# Morpheus_LDO.net
KiCad netlist of a schematic drawn in Altium Designer
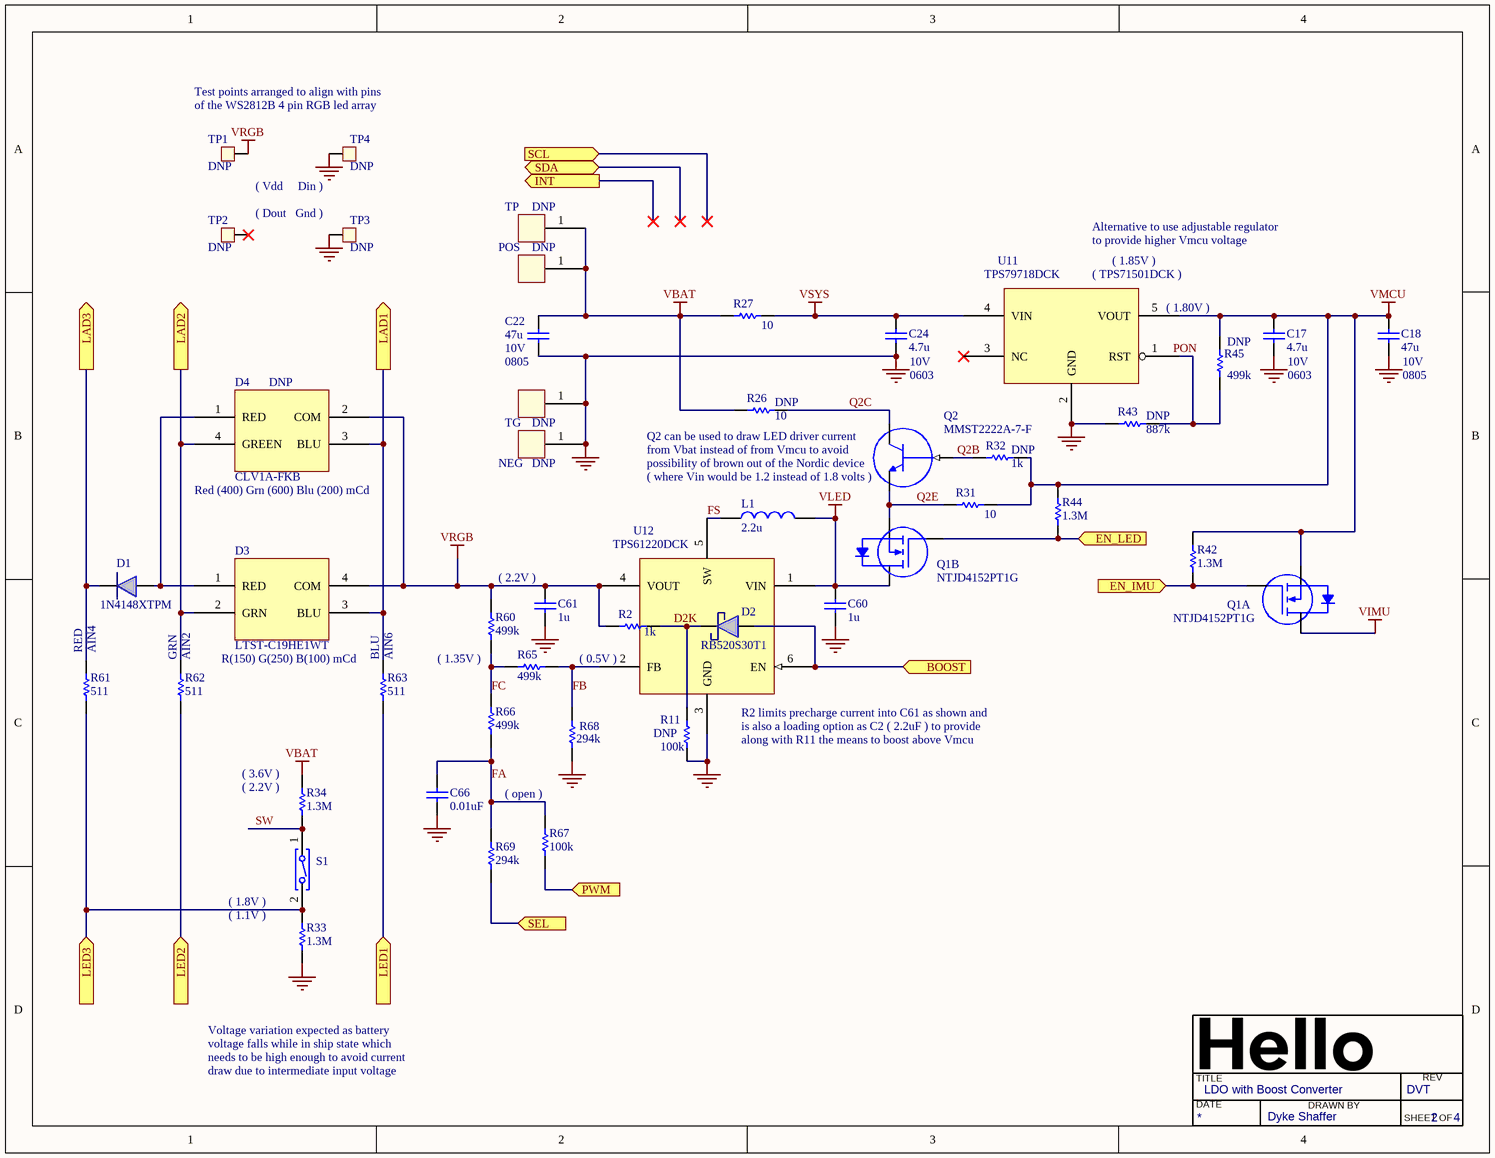
[diagram p0: Morpheus_LDO.SchDoc]

(export (version "E")
  (design (tool "Eeschema 10.0.6"))
  (components
    (comp (ref "C17")
      (value "4.7u")
      (footprint "CAP0603_SENSE_DVT")
      (description "Chip capacitor")
      (fields (field (name "SIZE") "0603") (field (name "TOLERANCE") "20%") (field (name "VOLTAGE") "10V"))
      (libsource (lib "Hello") (part "C_4.7u_20_10_X5R_0603"))
    )
    (comp (ref "C18")
      (value "47u")
      (footprint "CAP0805_SENSE_DVT")
      (description "Chip capacitor")
      (fields (field (name "SIZE") "0805") (field (name "TOLERANCE") "20%") (field (name "VOLTAGE") "10V"))
      (libsource (lib "Hello") (part "C_47u_20_10_X5R_0805"))
    )
    (comp (ref "C22")
      (value "47u")
      (footprint "CAP0805_SENSE_DVT")
      (description "Chip capacitor")
      (fields (field (name "SIZE") "0805") (field (name "TOLERANCE") "20%") (field (name "VOLTAGE") "10V"))
      (libsource (lib "Hello") (part "C_47u_20_10_X5R_0805"))
    )
    (comp (ref "C24")
      (value "4.7u")
      (footprint "CAP0603_SENSE_DVT")
      (description "Chip capacitor")
      (fields (field (name "SIZE") "0603") (field (name "TOLERANCE") "20%") (field (name "VOLTAGE") "10V"))
      (libsource (lib "Hello") (part "C_4.7u_20_10_X5R_0603"))
    )
    (comp (ref "C60")
      (value "1u")
      (footprint "CAP0402_SENSE_DVT")
      (description "Chip capacitor")
      (fields (field (name "TOLERANCE") "10%") (field (name "VOLTAGE") "6.3V"))
      (libsource (lib "Hello") (part "C_1u_10_6.3_X5R_0402"))
    )
    (comp (ref "C61")
      (value "1u")
      (footprint "CAP0402_SENSE_DVT")
      (description "Chip capacitor")
      (fields (field (name "TOLERANCE") "10%") (field (name "VOLTAGE") "6.3V"))
      (libsource (lib "Hello") (part "C_1u_10_6.3_X5R_0402"))
    )
    (comp (ref "C66")
      (value "0.01uF")
      (footprint "CAP0402_SENSE_DVT")
      (description "Chip capacitor")
      (fields (field (name "TOLERANCE") "10%") (field (name "VOLTAGE") "50"))
      (libsource (lib "Hello") (part "C_10000p_10_50_X7R_0402"))
    )
    (comp (ref "D1")
      (value "1N4148XTPM")
      (footprint "SOD523")
      (description "Silicon diode, 30V 200mA")
      (libsource (lib "Hello") (part "1N4148XTPM"))
    )
    (comp (ref "D2")
      (value "RB520S30T1")
      (footprint "SOD523")
      (description "Schottky diode, 30V 200mA")
      (libsource (lib "dykes") (part "RB520S30T1"))
    )
    (comp (ref "D3")
      (value "LTST-C19HE1WT")
      (footprint "DFN120X85P160X160X35-4R")
      (description "RGB LED Array")
      (fields (field (name "ALTIUM_VALUE") "R(150) G(250) B(100) mCd"))
      (libsource (lib "dykes") (part "LTST-C19HE1WT"))
    )
    (comp (ref "D4")
      (value "DNP")
      (footprint "PLCC150X290P280X320X35-4")
      (description "RGB LED Array")
      (fields
        (field (name "PN") "CLV1A-FKB")
        (field (name "ALTIUM_VALUE") "Red (400) Grn (600) Blu (200) mCd")
      )
      (libsource (lib "Hello") (part "CLV1A-FKB"))
    )
    (comp (ref "L1")
      (value "2.2u")
      (footprint "IND_1206")
      (description "SMD power inductor, 2.2uH")
      (fields (field (name "TOLERANCE") "20%"))
      (libsource (lib "Hello") (part "L_2.2u_1206"))
    )
    (comp (ref "NEG")
      (value "DNP")
      (footprint "TP0875x050")
      (description "Single-pad test point")
      (libsource (lib "Mopd") (part "5016"))
    )
    (comp (ref "POS")
      (value "DNP")
      (footprint "TP0875x050")
      (description "Single-pad test point")
      (libsource (lib "Mopd") (part "5016"))
    )
    (comp (ref "Q1")
      (value "NTJD4152PT1G")
      (footprint "SOT65P212X110-6N")
      (description "Vishay Dual N-Channel MOSFET 1.2v drive 20V 0.88A")
      (libsource (lib "Hello") (part "NTJD4152PT1G"))
    )
    (comp (ref "Q2")
      (value "MMST2222A")
      (footprint "SOT-323")
      (description "NPN Transistor, 20V, 600mA")
      (fields (field (name "PN") "MMST2222A-7-F"))
      (libsource (lib "Hello") (part "MMST2222A"))
    )
    (comp (ref "R2")
      (value "1k")
      (footprint "RES0402_SENSE_DVT")
      (description "Chip Resistor")
      (fields (field (name "TOLERANCE") "1 %") (field (name "POWER") "0.1 W"))
      (libsource (lib "Hello") (part "R_1k_1_0.1_0402"))
    )
    (comp (ref "R11")
      (value "DNP")
      (footprint "RES0402_SENSE_DVT")
      (description "Chip Resistor")
      (fields
        (field (name "ALTIUM_VALUE") "100k")
        (field (name "TOLERANCE") "1 %")
        (field (name "POWER") "0.1 W")
      )
      (libsource (lib "Hello") (part "R_100k_1_0.1_0402"))
    )
    (comp (ref "R26")
      (value "DNP")
      (footprint "RES0402_SENSE_DVT")
      (description "Chip Resistor")
      (fields
        (field (name "ALTIUM_VALUE") "10")
        (field (name "TOLERANCE") "1 %")
        (field (name "POWER") "0.1 W")
      )
      (libsource (lib "Hello") (part "R_10_1_0.1_0402"))
    )
    (comp (ref "R27")
      (value "10")
      (footprint "RES0402_SENSE_DVT")
      (description "Chip Resistor")
      (fields (field (name "TOLERANCE") "1 %") (field (name "POWER") "0.1 W"))
      (libsource (lib "Hello") (part "R_10_1_0.1_0402"))
    )
    (comp (ref "R31")
      (value "10")
      (footprint "RES0402_SENSE_DVT")
      (description "Chip Resistor")
      (fields (field (name "TOLERANCE") "1 %") (field (name "POWER") "0.1 W"))
      (libsource (lib "Hello") (part "R_10_1_0.1_0402"))
    )
    (comp (ref "R32")
      (value "DNP")
      (footprint "RES0402_SENSE_DVT")
      (description "Chip Resistor")
      (fields
        (field (name "ALTIUM_VALUE") "1k")
        (field (name "TOLERANCE") "1 %")
        (field (name "POWER") "0.1 W")
      )
      (libsource (lib "Hello") (part "R_1k_1_0.1_0402"))
    )
    (comp (ref "R33")
      (value "1.3M")
      (footprint "RES0402_SENSE_DVT")
      (description "Chip Resistor")
      (fields (field (name "TOLERANCE") "5 %") (field (name "POWER") "0.1 W"))
      (libsource (lib "Hello") (part "R_1.3M_5_0.1_0402"))
    )
    (comp (ref "R34")
      (value "1.3M")
      (footprint "RES0402_SENSE_DVT")
      (description "Chip Resistor")
      (fields (field (name "TOLERANCE") "5 %") (field (name "POWER") "0.1 W"))
      (libsource (lib "Hello") (part "R_1.3M_5_0.1_0402"))
    )
    (comp (ref "R42")
      (value "1.3M")
      (footprint "RES0402_SENSE_DVT")
      (description "Chip Resistor")
      (fields (field (name "TOLERANCE") "5 %") (field (name "POWER") "0.1 W"))
      (libsource (lib "Hello") (part "R_1.3M_5_0.1_0402"))
    )
    (comp (ref "R43")
      (value "DNP")
      (footprint "RES0402_SENSE_DVT")
      (description "Chip Resistor")
      (fields
        (field (name "ALTIUM_VALUE") "887k")
        (field (name "TOLERANCE") "1 %")
        (field (name "POWER") "0.1 W")
      )
      (libsource (lib "Hello") (part "R_887k_1_0.1_0402"))
    )
    (comp (ref "R44")
      (value "1.3M")
      (footprint "RES0402_SENSE_DVT")
      (description "Chip Resistor")
      (fields (field (name "TOLERANCE") "5 %") (field (name "POWER") "0.1 W"))
      (libsource (lib "Hello") (part "R_1.3M_5_0.1_0402"))
    )
    (comp (ref "R45")
      (value "DNP")
      (footprint "RES0402_SENSE_DVT")
      (description "Chip Resistor")
      (fields
        (field (name "ALTIUM_VALUE") "499k")
        (field (name "TOLERANCE") "1 %")
        (field (name "POWER") "0.1 W")
      )
      (libsource (lib "Hello") (part "R_499k_1_0.1_0402"))
    )
    (comp (ref "R60")
      (value "499k")
      (footprint "RES0402_SENSE_DVT")
      (description "Chip Resistor")
      (fields (field (name "TOLERANCE") "1 %") (field (name "POWER") "0.1 W"))
      (libsource (lib "Hello") (part "R_499k_1_0.1_0402"))
    )
    (comp (ref "R61")
      (value "511")
      (footprint "RES0402_SENSE_DVT")
      (description "Chip Resistor")
      (fields (field (name "TOLERANCE") "1 %") (field (name "POWER") "0.1 W"))
      (libsource (lib "Hello") (part "R_511_1_0.1_0402"))
    )
    (comp (ref "R62")
      (value "511")
      (footprint "RES0402_SENSE_DVT")
      (description "Chip Resistor")
      (fields (field (name "TOLERANCE") "1 %") (field (name "POWER") "0.1 W"))
      (libsource (lib "Hello") (part "R_511_1_0.1_0402"))
    )
    (comp (ref "R63")
      (value "511")
      (footprint "RES0402_SENSE_DVT")
      (description "Chip Resistor")
      (fields (field (name "TOLERANCE") "1 %") (field (name "POWER") "0.1 W"))
      (libsource (lib "Hello") (part "R_511_1_0.1_0402"))
    )
    (comp (ref "R65")
      (value "499k")
      (footprint "RES0402_SENSE_DVT")
      (description "Chip Resistor")
      (fields (field (name "TOLERANCE") "1 %") (field (name "POWER") "0.1 W"))
      (libsource (lib "Hello") (part "R_499k_1_0.1_0402"))
    )
    (comp (ref "R66")
      (value "499k")
      (footprint "RES0402_SENSE_DVT")
      (description "Chip Resistor")
      (fields (field (name "TOLERANCE") "1 %") (field (name "POWER") "0.1 W"))
      (libsource (lib "Hello") (part "R_499k_1_0.1_0402"))
    )
    (comp (ref "R67")
      (value "100k")
      (footprint "RES0402_SENSE_DVT")
      (description "Chip Resistor")
      (fields (field (name "TOLERANCE") "1 %") (field (name "POWER") "0.1 W"))
      (libsource (lib "Hello") (part "R_100k_1_0.1_0402"))
    )
    (comp (ref "R68")
      (value "294k")
      (footprint "RES0402_SENSE_DVT")
      (description "Chip Resistor")
      (fields (field (name "TOLERANCE") "1 %") (field (name "POWER") "0.1 W"))
      (libsource (lib "Hello") (part "R_294k_1_0.1_0402"))
    )
    (comp (ref "R69")
      (value "294k")
      (footprint "RES0402_SENSE_DVT")
      (description "Chip Resistor")
      (fields (field (name "TOLERANCE") "1 %") (field (name "POWER") "0.1 W"))
      (libsource (lib "Hello") (part "R_294k_1_0.1_0402"))
    )
    (comp (ref "S1")
      (value "REED_SPST_NO")
      (footprint "REED-10x1.8")
      (description "SWITCH REED SPST NO")
      (libsource (lib "Hello") (part "SW_REED_SPST_NO"))
    )
    (comp (ref "TG")
      (value "DNP")
      (footprint "TP0875x050")
      (description "Single-pad test point")
      (libsource (lib "Mopd") (part "5016"))
    )
    (comp (ref "TP")
      (value "DNP")
      (footprint "TP0875x050")
      (description "Single-pad test point")
      (libsource (lib "Mopd") (part "5016"))
    )
    (comp (ref "TP1")
      (value "DNP")
      (footprint "TP-0.8")
      (description "testpoint")
      (libsource (lib "Hello") (part "TP-0.8"))
    )
    (comp (ref "TP2")
      (value "DNP")
      (footprint "TP-0.8")
      (description "testpoint")
      (libsource (lib "Hello") (part "TP-0.8"))
    )
    (comp (ref "TP3")
      (value "DNP")
      (footprint "TP-0.8")
      (description "testpoint")
      (libsource (lib "") (part "TP-0.8_1"))
    )
    (comp (ref "TP4")
      (value "DNP")
      (footprint "TP-0.8")
      (description "testpoint")
      (libsource (lib "") (part "TP-0.8_1"))
    )
    (comp (ref "U11")
      (value "TPS79718DCK")
      (footprint "SOT65P212X110-5N")
      (description "LDO 1.8V SC70-5")
      (libsource (lib "Hello") (part "TPS79718DCK"))
    )
    (comp (ref "U12")
      (value "TPS61220DCK")
      (footprint "SOT65P212X110-6N")
      (description "Boost Converter")
      (libsource (lib "dykes") (part "TPS61220"))
    )
  )
  (nets
    (net (code "1") (name "/BOOST") (class "Default")
      (node (ref "D2") (pin "2") (pinfunction "Anode_2") (pintype "passive"))
      (node (ref "U12") (pin "6") (pinfunction "EN_6") (pintype "input"))
    )
    (net (code "2") (name "/D2K") (class "Default")
      (node (ref "D2") (pin "1") (pinfunction "Cathode_1") (pintype "passive"))
      (node (ref "R11") (pin "2") (pinfunction "2_2") (pintype "passive"))
      (node (ref "R2") (pin "2") (pinfunction "2_2") (pintype "passive"))
    )
    (net (code "3") (name "/EN_IMU") (class "Default")
      (node (ref "Q1") (pin "2") (pinfunction "G1_2") (pintype "passive"))
      (node (ref "R42") (pin "1") (pinfunction "1_1") (pintype "passive"))
    )
    (net (code "4") (name "/EN_LED") (class "Default")
      (node (ref "Q1") (pin "5") (pinfunction "G2_5") (pintype "passive"))
      (node (ref "R44") (pin "1") (pinfunction "1_1") (pintype "passive"))
    )
    (net (code "5") (name "/FA") (class "Default")
      (node (ref "C66") (pin "2") (pinfunction "2_2") (pintype "passive"))
      (node (ref "R66") (pin "1") (pinfunction "1_1") (pintype "passive"))
      (node (ref "R67") (pin "2") (pinfunction "2_2") (pintype "passive"))
      (node (ref "R69") (pin "2") (pinfunction "2_2") (pintype "passive"))
    )
    (net (code "6") (name "/FB") (class "Default")
      (node (ref "R65") (pin "1") (pinfunction "1_1") (pintype "passive"))
      (node (ref "R68") (pin "2") (pinfunction "2_2") (pintype "passive"))
      (node (ref "U12") (pin "2") (pinfunction "FB_2") (pintype "passive"))
    )
    (net (code "7") (name "/FC") (class "Default")
      (node (ref "R60") (pin "1") (pinfunction "1_1") (pintype "passive"))
      (node (ref "R65") (pin "2") (pinfunction "2_2") (pintype "passive"))
      (node (ref "R66") (pin "2") (pinfunction "2_2") (pintype "passive"))
    )
    (net (code "8") (name "/FS") (class "Default")
      (node (ref "L1") (pin "2") (pintype "passive"))
      (node (ref "U12") (pin "5") (pinfunction "SW_5") (pintype "passive"))
    )
    (net (code "10") (name "/LAD1") (class "Default")
      (node (ref "D3") (pin "3") (pinfunction "BLU_3") (pintype "passive"))
      (node (ref "D4") (pin "3") (pinfunction "BLU_3") (pintype "passive"))
      (node (ref "R63") (pin "2") (pinfunction "2_2") (pintype "passive"))
    )
    (net (code "11") (name "/LAD2") (class "Default")
      (node (ref "D3") (pin "2") (pinfunction "GRN_2") (pintype "passive"))
      (node (ref "D4") (pin "4") (pinfunction "GREEN_4") (pintype "passive"))
      (node (ref "R62") (pin "2") (pinfunction "2_2") (pintype "passive"))
    )
    (net (code "12") (name "/LAD3") (class "Default")
      (node (ref "D1") (pin "1") (pinfunction "Cathode_1") (pintype "passive"))
      (node (ref "R61") (pin "2") (pinfunction "2_2") (pintype "passive"))
    )
    (net (code "13") (name "/LED1") (class "Default")
      (node (ref "R63") (pin "1") (pinfunction "1_1") (pintype "passive"))
    )
    (net (code "14") (name "/LED2") (class "Default")
      (node (ref "R62") (pin "1") (pinfunction "1_1") (pintype "passive"))
    )
    (net (code "15") (name "/LED3") (class "Default")
      (node (ref "R33") (pin "2") (pinfunction "2_2") (pintype "passive"))
      (node (ref "R61") (pin "1") (pinfunction "1_1") (pintype "passive"))
      (node (ref "S1") (pin "2") (pinfunction "2_2") (pintype "passive"))
    )
    (net (code "17") (name "/PWM") (class "Default")
      (node (ref "R67") (pin "1") (pinfunction "1_1") (pintype "passive"))
    )
    (net (code "18") (name "/Q2B") (class "Default")
      (node (ref "Q2") (pin "1") (pinfunction "IN_1") (pintype "input"))
      (node (ref "R32") (pin "1") (pinfunction "1_1") (pintype "passive"))
    )
    (net (code "19") (name "/Q2C") (class "Default")
      (node (ref "Q2") (pin "3") (pinfunction "OUT_3") (pintype "open_collector"))
      (node (ref "R26") (pin "2") (pinfunction "2_2") (pintype "passive"))
    )
    (net (code "20") (name "/Q2E") (class "Default")
      (node (ref "Q1") (pin "4") (pinfunction "S2_4") (pintype "passive"))
      (node (ref "Q2") (pin "2") (pinfunction "GND_2") (pintype "power_in"))
      (node (ref "R31") (pin "1") (pinfunction "1_1") (pintype "passive"))
    )
    (net (code "23") (name "/SEL") (class "Default")
      (node (ref "R69") (pin "1") (pinfunction "1_1") (pintype "passive"))
    )
    (net (code "24") (name "/SW") (class "Default")
      (node (ref "R34") (pin "1") (pinfunction "1_1") (pintype "passive"))
      (node (ref "S1") (pin "1") (pinfunction "1_1") (pintype "passive"))
    )
    (net (code "25") (name "GND") (class "Default")
      (node (ref "C17") (pin "1") (pinfunction "1_1") (pintype "passive"))
      (node (ref "C18") (pin "1") (pinfunction "1_1") (pintype "passive"))
      (node (ref "C22") (pin "1") (pinfunction "1_1") (pintype "passive"))
      (node (ref "C24") (pin "1") (pinfunction "1_1") (pintype "passive"))
      (node (ref "C60") (pin "1") (pinfunction "1_1") (pintype "passive"))
      (node (ref "C61") (pin "1") (pinfunction "1_1") (pintype "passive"))
      (node (ref "C66") (pin "1") (pinfunction "1_1") (pintype "passive"))
      (node (ref "NEG") (pin "1") (pinfunction "1_1") (pintype "passive"))
      (node (ref "R11") (pin "1") (pinfunction "1_1") (pintype "passive"))
      (node (ref "R33") (pin "1") (pinfunction "1_1") (pintype "passive"))
      (node (ref "R43") (pin "1") (pinfunction "1_1") (pintype "passive"))
      (node (ref "R68") (pin "1") (pinfunction "1_1") (pintype "passive"))
      (node (ref "TG") (pin "1") (pinfunction "1_1") (pintype "passive"))
      (node (ref "TP3") (pin "1") (pinfunction "1_1") (pintype "passive"))
      (node (ref "TP4") (pin "1") (pinfunction "1_1") (pintype "passive"))
      (node (ref "U11") (pin "2") (pinfunction "GND_2") (pintype "power_in"))
      (node (ref "U12") (pin "3") (pinfunction "GND_3") (pintype "power_in"))
    )
    (net (code "26") (name "Net-(D1-Anode)") (class "Default")
      (node (ref "D1") (pin "2") (pinfunction "Anode_2") (pintype "passive"))
      (node (ref "D3") (pin "1") (pinfunction "RED_1") (pintype "passive"))
      (node (ref "D4") (pin "1") (pinfunction "RED_1") (pintype "passive"))
    )
    (net (code "27") (name "Net-(U11-RST)") (class "Default")
      (node (ref "R43") (pin "2") (pinfunction "2_2") (pintype "passive"))
      (node (ref "R45") (pin "1") (pinfunction "1_1") (pintype "passive"))
      (node (ref "U11") (pin "1") (pinfunction "RST_1") (pintype "open_collector"))
    )
    (net (code "28") (name "VBAT") (class "Default")
      (node (ref "C22") (pin "2") (pinfunction "2_2") (pintype "passive"))
      (node (ref "POS") (pin "1") (pinfunction "1_1") (pintype "passive"))
      (node (ref "R26") (pin "1") (pinfunction "1_1") (pintype "passive"))
      (node (ref "R27") (pin "1") (pinfunction "1_1") (pintype "passive"))
      (node (ref "R34") (pin "2") (pinfunction "2_2") (pintype "passive"))
      (node (ref "TP") (pin "1") (pinfunction "1_1") (pintype "passive"))
    )
    (net (code "29") (name "VIMU") (class "Default")
      (node (ref "Q1") (pin "6") (pinfunction "D1_6") (pintype "passive"))
    )
    (net (code "30") (name "VLED") (class "Default")
      (node (ref "C60") (pin "2") (pinfunction "2_2") (pintype "passive"))
      (node (ref "L1") (pin "1") (pintype "passive"))
      (node (ref "Q1") (pin "3") (pinfunction "D2_3") (pintype "passive"))
      (node (ref "U12") (pin "1") (pinfunction "VIN_1") (pintype "power_in"))
    )
    (net (code "31") (name "VMCU") (class "Default")
      (node (ref "C17") (pin "2") (pinfunction "2_2") (pintype "passive"))
      (node (ref "C18") (pin "2") (pinfunction "2_2") (pintype "passive"))
      (node (ref "Q1") (pin "1") (pinfunction "S1_1") (pintype "passive"))
      (node (ref "R31") (pin "2") (pinfunction "2_2") (pintype "passive"))
      (node (ref "R32") (pin "2") (pinfunction "2_2") (pintype "passive"))
      (node (ref "R42") (pin "2") (pinfunction "2_2") (pintype "passive"))
      (node (ref "R44") (pin "2") (pinfunction "2_2") (pintype "passive"))
      (node (ref "R45") (pin "2") (pinfunction "2_2") (pintype "passive"))
      (node (ref "U11") (pin "5") (pinfunction "VOUT_5") (pintype "power_in"))
    )
    (net (code "32") (name "VRGB") (class "Default")
      (node (ref "C61") (pin "2") (pinfunction "2_2") (pintype "passive"))
      (node (ref "D3") (pin "4") (pinfunction "COM_4") (pintype "passive"))
      (node (ref "D4") (pin "2") (pinfunction "COM_2") (pintype "passive"))
      (node (ref "R2") (pin "1") (pinfunction "1_1") (pintype "passive"))
      (node (ref "R60") (pin "2") (pinfunction "2_2") (pintype "passive"))
      (node (ref "TP1") (pin "1") (pinfunction "1_1") (pintype "passive"))
      (node (ref "U12") (pin "4") (pinfunction "VOUT_4") (pintype "power_in"))
    )
    (net (code "33") (name "VSYS") (class "Default")
      (node (ref "C24") (pin "2") (pinfunction "2_2") (pintype "passive"))
      (node (ref "R27") (pin "2") (pinfunction "2_2") (pintype "passive"))
      (node (ref "U11") (pin "4") (pinfunction "VIN_4") (pintype "power_in"))
    )
    (net (code "34") (name "unconnected-(TP2-Pad1)") (class "Default")
      (node (ref "TP2") (pin "1") (pinfunction "1_1") (pintype "passive+no_connect"))
    )
    (net (code "35") (name "unconnected-(U11-NC-Pad3)") (class "Default")
      (node (ref "U11") (pin "3") (pinfunction "NC_3") (pintype "passive+no_connect"))
    )
  )
)
